# Analog_Hall_Board.net
KiCad netlist of a schematic drawn in Altium Designer
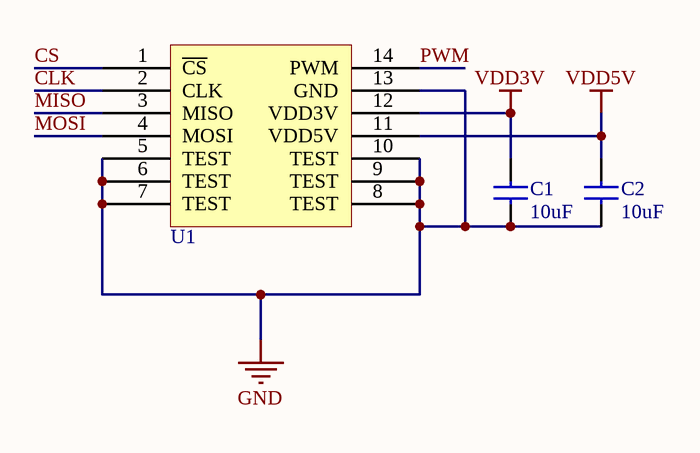
[diagram p0: Analog Hall Board.SchDoc]

(export (version "E")
  (design (tool "Eeschema 10.0.6"))
  (components
    (comp (ref "C1")
      (value "10uF")
      (footprint "0603_cap")
      (description "CAP CERM 0603")
      (fields (field (name "Comment") "CAP 0603"))
      (libsource (lib "Nutz") (part "C_0603"))
    )
    (comp (ref "C2")
      (value "10uF")
      (footprint "0603_cap")
      (description "CAP CERM 0603")
      (fields (field (name "Comment") "CAP 0603"))
      (libsource (lib "Nutz") (part "C_0603"))
    )
    (comp (ref "U1")
      (value "AS5048A Analog Hall Sensor")
      (footprint "TSOP65P640X120-14N")
      (description "IC ENCODER ROTARY 14-TSSOP")
      (fields (field (name "MANUFACTURER") "ams") (field (name "SVP CREATOR") "Thomas Daede"))
      (libsource (lib "d1_SchLib") (part "U_AS5048A"))
    )
  )
  (nets
    (net (code "1") (name "/CLK") (class "Default")
      (node (ref "U1") (pin "2") (pinfunction "CLK_2") (pintype "passive"))
    )
    (net (code "2") (name "/CS") (class "Default")
      (node (ref "U1") (pin "1") (pinfunction "~{CS}_1") (pintype "passive"))
    )
    (net (code "3") (name "/MISO") (class "Default")
      (node (ref "U1") (pin "3") (pinfunction "MISO_3") (pintype "passive"))
    )
    (net (code "4") (name "/MOSI") (class "Default")
      (node (ref "U1") (pin "4") (pinfunction "MOSI_4") (pintype "passive"))
    )
    (net (code "5") (name "/PWM") (class "Default")
      (node (ref "U1") (pin "14") (pinfunction "PWM_14") (pintype "passive"))
    )
    (net (code "6") (name "GND") (class "Default")
      (node (ref "C1") (pin "2") (pinfunction "2_2") (pintype "passive"))
      (node (ref "C2") (pin "2") (pinfunction "2_2") (pintype "passive"))
      (node (ref "U1") (pin "10") (pinfunction "TEST_10") (pintype "passive"))
      (node (ref "U1") (pin "13") (pinfunction "GND_13") (pintype "passive"))
      (node (ref "U1") (pin "5") (pinfunction "TEST_5") (pintype "passive"))
      (node (ref "U1") (pin "6") (pinfunction "TEST_6") (pintype "passive"))
      (node (ref "U1") (pin "7") (pinfunction "TEST_7") (pintype "passive"))
      (node (ref "U1") (pin "8") (pinfunction "TEST_8") (pintype "passive"))
      (node (ref "U1") (pin "9") (pinfunction "TEST_9") (pintype "passive"))
    )
    (net (code "7") (name "VDD3V") (class "Default")
      (node (ref "C1") (pin "1") (pinfunction "1_1") (pintype "passive"))
      (node (ref "U1") (pin "12") (pinfunction "VDD3V_12") (pintype "passive"))
    )
    (net (code "8") (name "VDD5V") (class "Default")
      (node (ref "C2") (pin "1") (pinfunction "1_1") (pintype "passive"))
      (node (ref "U1") (pin "11") (pinfunction "VDD5V_11") (pintype "passive"))
    )
  )
)
